# SWARMESH04.net
KiCad netlist of a schematic drawn in EAGLE
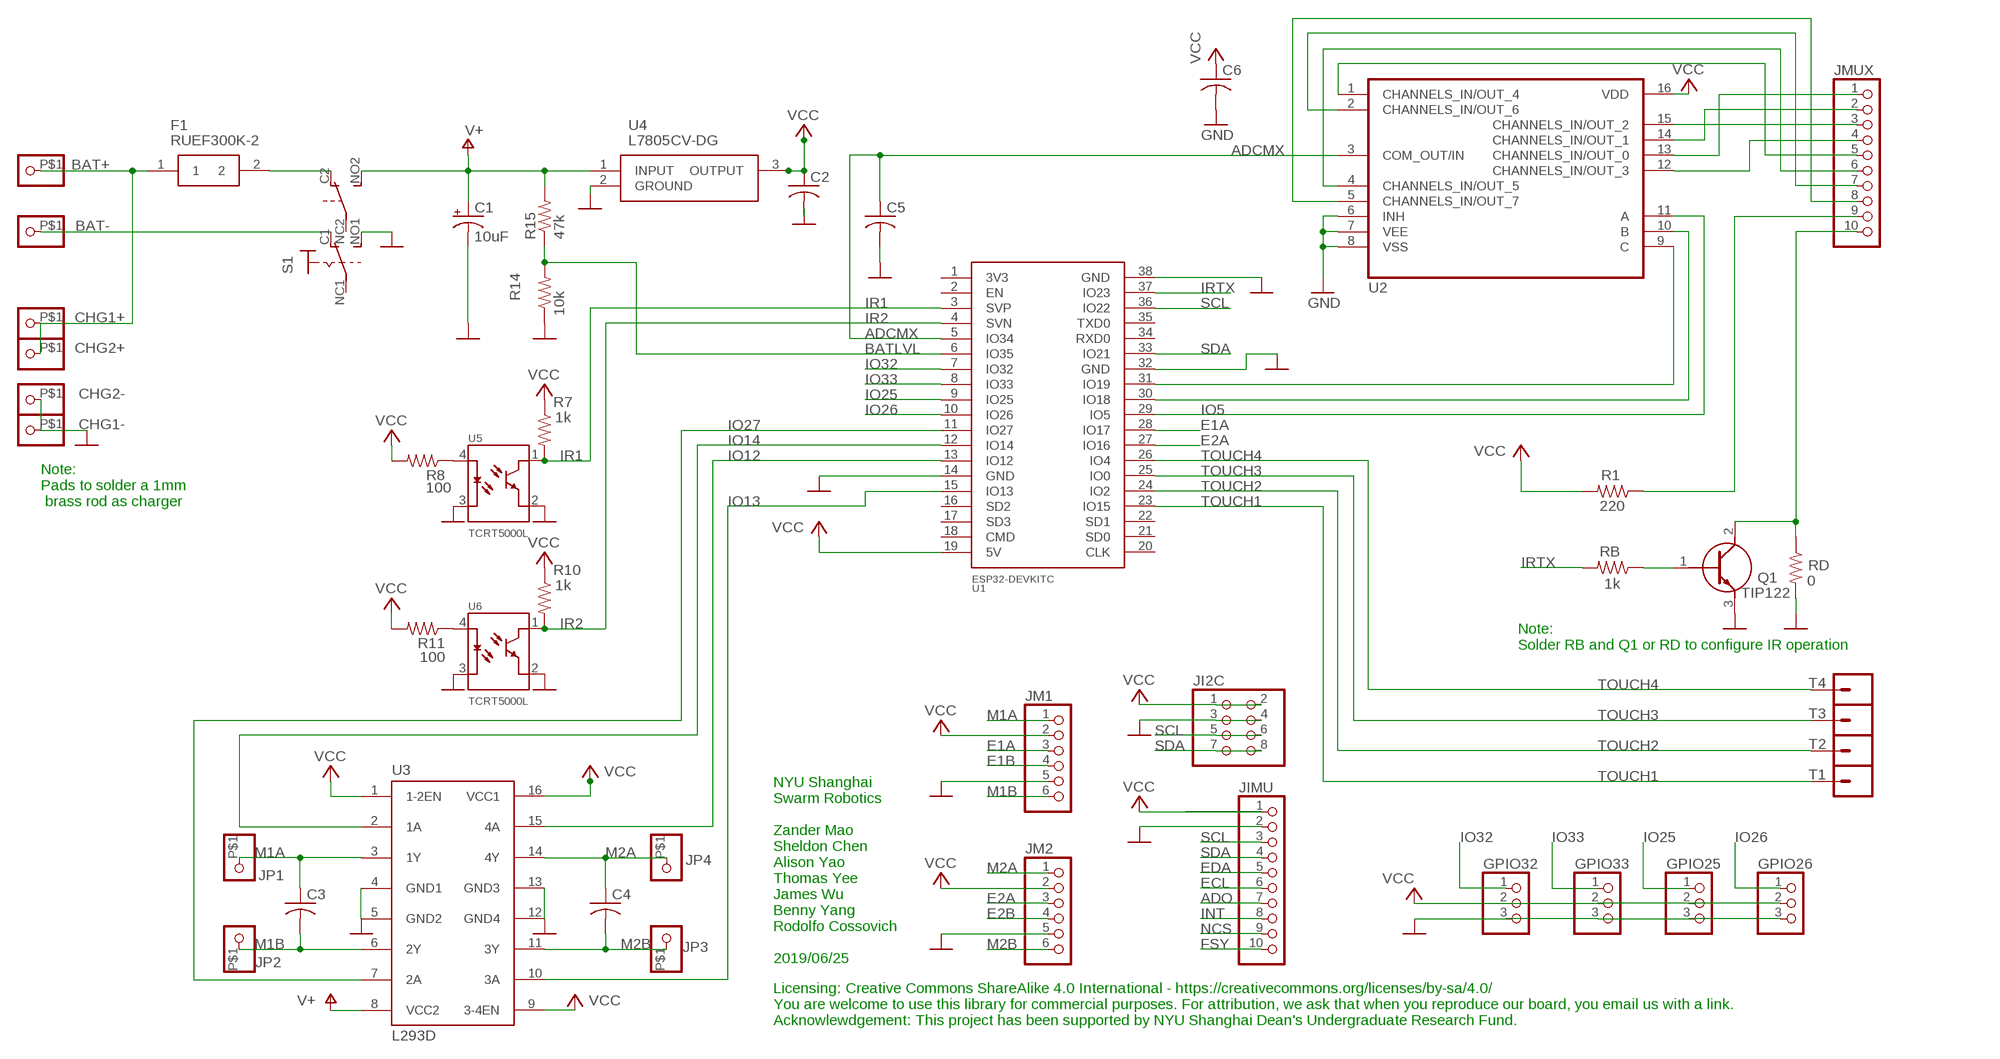
[diagram p0: schematic, sheet 1]

(export (version "E")
  (design (tool "Eeschema 10.0.6"))
  (components
    (comp (ref "BAT+")
      (value "PINHD-1X1-BIGPOGO")
      (footprint "eagle-import:1X1-BIGPOGO")
      (libsource (lib "eagle-import") (part "PINHD-1X1-BIGPOGO"))
    )
    (comp (ref "BAT-")
      (value "PINHD-1X1-BIGPOGO")
      (footprint "eagle-import:1X1-BIGPOGO")
      (libsource (lib "eagle-import") (part "PINHD-1X1-BIGPOGO"))
    )
    (comp (ref "C1")
      (value "10uF")
      (footprint "eagle-import:E2-5")
      (libsource (lib "eagle-import") (part "CPOL-USE2-5"))
    )
    (comp (ref "C2")
      (value "C-US025-030X050")
      (footprint "eagle-import:C025-030X050")
      (libsource (lib "eagle-import") (part "C-US025-030X050"))
    )
    (comp (ref "C3")
      (value "C-US025-025X050")
      (footprint "eagle-import:C025-025X050")
      (libsource (lib "eagle-import") (part "C-US025-025X050"))
    )
    (comp (ref "C4")
      (value "C-US025-025X050")
      (footprint "eagle-import:C025-025X050")
      (libsource (lib "eagle-import") (part "C-US025-025X050"))
    )
    (comp (ref "C5")
      (value "C-US025-030X050")
      (footprint "eagle-import:C025-030X050")
      (libsource (lib "eagle-import") (part "C-US025-030X050"))
    )
    (comp (ref "C6")
      (value "C-US025-025X050")
      (footprint "eagle-import:C025-025X050")
      (libsource (lib "eagle-import") (part "C-US025-025X050"))
    )
    (comp (ref "CHG1+")
      (value "PINHD-1X1-BIGPOGO")
      (footprint "eagle-import:1X1-BIGPOGO")
      (libsource (lib "eagle-import") (part "PINHD-1X1-BIGPOGO"))
    )
    (comp (ref "CHG1-")
      (value "PINHD-1X1-BIGPOGO")
      (footprint "eagle-import:1X1-BIGPOGO")
      (libsource (lib "eagle-import") (part "PINHD-1X1-BIGPOGO"))
    )
    (comp (ref "CHG2+")
      (value "PINHD-1X1-BIGPOGO")
      (footprint "eagle-import:1X1-BIGPOGO")
      (libsource (lib "eagle-import") (part "PINHD-1X1-BIGPOGO"))
    )
    (comp (ref "CHG2-")
      (value "PINHD-1X1-BIGPOGO")
      (footprint "eagle-import:1X1-BIGPOGO")
      (libsource (lib "eagle-import") (part "PINHD-1X1-BIGPOGO"))
    )
    (comp (ref "F1")
      (value "RUEF300K-2")
      (footprint "eagle-import:RUEF300K2")
      (libsource (lib "eagle-import") (part "RUEF300K-2"))
    )
    (comp (ref "GPIO25")
      (value "PINHD-1X3")
      (footprint "eagle-import:1X03")
      (libsource (lib "eagle-import") (part "PINHD-1X3"))
    )
    (comp (ref "GPIO26")
      (value "PINHD-1X3")
      (footprint "eagle-import:1X03")
      (libsource (lib "eagle-import") (part "PINHD-1X3"))
    )
    (comp (ref "GPIO32")
      (value "PINHD-1X3")
      (footprint "eagle-import:1X03")
      (libsource (lib "eagle-import") (part "PINHD-1X3"))
    )
    (comp (ref "GPIO33")
      (value "PINHD-1X3")
      (footprint "eagle-import:1X03")
      (libsource (lib "eagle-import") (part "PINHD-1X3"))
    )
    (comp (ref "JI2C")
      (value "PINHD-2X4")
      (footprint "eagle-import:2X04")
      (libsource (lib "eagle-import") (part "PINHD-2X4"))
    )
    (comp (ref "JIMU")
      (value "PINHD-1X10")
      (footprint "eagle-import:1X10-BIG")
      (libsource (lib "eagle-import") (part "PINHD-1X10"))
    )
    (comp (ref "JM1")
      (value "PINHD-1X6")
      (footprint "eagle-import:1X06")
      (libsource (lib "eagle-import") (part "PINHD-1X6"))
    )
    (comp (ref "JM2")
      (value "PINHD-1X6")
      (footprint "eagle-import:1X06")
      (libsource (lib "eagle-import") (part "PINHD-1X6"))
    )
    (comp (ref "JMUX")
      (value "PINHD-1X10")
      (footprint "eagle-import:1X10-BIG")
      (libsource (lib "eagle-import") (part "PINHD-1X10"))
    )
    (comp (ref "JP1")
      (value "PINHD-1X1-BIGPOGO")
      (footprint "eagle-import:1X1-BIGPOGO")
      (libsource (lib "eagle-import") (part "adafruit_420_PINHD-1X1-BIGPOGO"))
    )
    (comp (ref "JP2")
      (value "PINHD-1X1-BIGPOGO")
      (footprint "eagle-import:1X1-BIGPOGO")
      (libsource (lib "eagle-import") (part "adafruit_420_PINHD-1X1-BIGPOGO"))
    )
    (comp (ref "JP3")
      (value "PINHD-1X1-BIGPOGO")
      (footprint "eagle-import:1X1-BIGPOGO")
      (libsource (lib "eagle-import") (part "adafruit_420_PINHD-1X1-BIGPOGO"))
    )
    (comp (ref "JP4")
      (value "PINHD-1X1-BIGPOGO")
      (footprint "eagle-import:1X1-BIGPOGO")
      (libsource (lib "eagle-import") (part "adafruit_420_PINHD-1X1-BIGPOGO"))
    )
    (comp (ref "Q1")
      (value "TIP122")
      (footprint "eagle-import:TO270P460X1020X2008-3P")
      (fields (field (name "MOUSER_PART_NUMBER") "511-TIP122"))
      (libsource (lib "eagle-import") (part "TIP122"))
    )
    (comp (ref "R1")
      (value "220")
      (footprint "eagle-import:0207_9")
      (libsource (lib "eagle-import") (part "R-US_0207/9"))
    )
    (comp (ref "R7")
      (value "1k")
      (footprint "eagle-import:0207_9")
      (libsource (lib "eagle-import") (part "R-US_0207/9"))
    )
    (comp (ref "R8")
      (value "100")
      (footprint "eagle-import:0207_9")
      (libsource (lib "eagle-import") (part "R-US_0207/9"))
    )
    (comp (ref "R10")
      (value "1k")
      (footprint "eagle-import:0207_9")
      (libsource (lib "eagle-import") (part "R-US_0207/9"))
    )
    (comp (ref "R11")
      (value "100")
      (footprint "eagle-import:0207_9")
      (libsource (lib "eagle-import") (part "R-US_0207/9"))
    )
    (comp (ref "R14")
      (value "10k")
      (footprint "eagle-import:0207_9")
      (libsource (lib "eagle-import") (part "R-US_0207/9"))
    )
    (comp (ref "R15")
      (value "47k")
      (footprint "eagle-import:0207_9")
      (libsource (lib "eagle-import") (part "R-US_0207/9"))
    )
    (comp (ref "RB")
      (value "1k")
      (footprint "eagle-import:0207_9")
      (libsource (lib "eagle-import") (part "R-US_0207/9"))
    )
    (comp (ref "RD")
      (value "0")
      (footprint "eagle-import:0207_9")
      (libsource (lib "eagle-import") (part "R-US_0207/9"))
    )
    (comp (ref "S1")
      (value "SWITCH_320-938")
      (footprint "eagle-import:PS22F03")
      (libsource (lib "eagle-import") (part "SWITCH_320-938"))
    )
    (comp (ref "T1")
      (value "CONN_01SPRING-CONN")
      (footprint "eagle-import:SPRING-CONNECTOR")
      (libsource (lib "eagle-import") (part "CONN_01SPRING-CONN"))
    )
    (comp (ref "T2")
      (value "CONN_01SPRING-CONN")
      (footprint "eagle-import:SPRING-CONNECTOR")
      (libsource (lib "eagle-import") (part "CONN_01SPRING-CONN"))
    )
    (comp (ref "T3")
      (value "CONN_01SPRING-CONN")
      (footprint "eagle-import:SPRING-CONNECTOR")
      (libsource (lib "eagle-import") (part "CONN_01SPRING-CONN"))
    )
    (comp (ref "T4")
      (value "CONN_01SPRING-CONN")
      (footprint "eagle-import:SPRING-CONNECTOR")
      (libsource (lib "eagle-import") (part "CONN_01SPRING-CONN"))
    )
    (comp (ref "U1")
      (value "ESP32DEVKITC")
      (footprint "eagle-import:ESP32-DEVKITC")
      (libsource (lib "eagle-import") (part "ESP32DEVKITC"))
    )
    (comp (ref "U2")
      (value "CD4051BEE4")
      (footprint "eagle-import:CD4051BEE4DIP")
      (libsource (lib "eagle-import") (part "CD4051BEE4"))
    )
    (comp (ref "U3")
      (value "L293D")
      (footprint "eagle-import:DIL16")
      (libsource (lib "eagle-import") (part "L293D"))
    )
    (comp (ref "U4")
      (value "L7805CV-DG")
      (footprint "eagle-import:TO270P460X1020X2008-3P")
      (fields (field (name "MOUSER_PART_NUMBER") "511-L7805CV-DG") (field (name "RS_PART_NUMBER") "7931346P"))
      (libsource (lib "eagle-import") (part "L7805CV-DG"))
    )
    (comp (ref "U5")
      (value "TCRT5000L")
      (footprint "eagle-import:XDCR_TCRT5000L")
      (fields (field (name "MF") "Vishay Semiconductor"))
      (libsource (lib "eagle-import") (part "TCRT5000L"))
    )
    (comp (ref "U6")
      (value "TCRT5000L")
      (footprint "eagle-import:XDCR_TCRT5000L")
      (fields (field (name "MF") "Vishay Semiconductor"))
      (libsource (lib "eagle-import") (part "TCRT5000L"))
    )
  )
  (nets
    (net (code "1") (name "/ADCMX") (class "Default")
      (node (ref "C5") (pin "1") (pinfunction "1_1") (pintype "passive"))
      (node (ref "U1") (pin "5") (pinfunction "IO34_5") (pintype "bidirectional"))
      (node (ref "U2") (pin "3") (pinfunction "COM_OUT/IN_3") (pintype "bidirectional"))
    )
    (net (code "2") (name "/ADO") (class "Default")
      (node (ref "JIMU") (pin "7") (pinfunction "7_7") (pintype "passive"))
    )
    (net (code "3") (name "/BATLVL") (class "Default")
      (node (ref "R14") (pin "2") (pinfunction "2_2") (pintype "passive"))
      (node (ref "R15") (pin "1") (pinfunction "1_1") (pintype "passive"))
      (node (ref "U1") (pin "6") (pinfunction "IO35_6") (pintype "bidirectional"))
    )
    (net (code "4") (name "/E1A") (class "Default")
      (node (ref "JM1") (pin "3") (pinfunction "3_3") (pintype "passive"))
      (node (ref "U1") (pin "28") (pinfunction "IO17_28") (pintype "bidirectional"))
    )
    (net (code "5") (name "/E1B") (class "Default")
      (node (ref "JM1") (pin "4") (pinfunction "4_4") (pintype "passive"))
    )
    (net (code "6") (name "/E2A") (class "Default")
      (node (ref "JM2") (pin "3") (pinfunction "3_3") (pintype "passive"))
      (node (ref "U1") (pin "27") (pinfunction "IO16_27") (pintype "bidirectional"))
    )
    (net (code "7") (name "/E2B") (class "Default")
      (node (ref "JM2") (pin "4") (pinfunction "4_4") (pintype "passive"))
    )
    (net (code "8") (name "/ECL") (class "Default")
      (node (ref "JIMU") (pin "6") (pinfunction "6_6") (pintype "passive"))
    )
    (net (code "9") (name "/EDA") (class "Default")
      (node (ref "JIMU") (pin "5") (pinfunction "5_5") (pintype "passive"))
    )
    (net (code "10") (name "/FSY") (class "Default")
      (node (ref "JIMU") (pin "10") (pinfunction "10_10") (pintype "passive"))
    )
    (net (code "11") (name "/INT") (class "Default")
      (node (ref "JIMU") (pin "8") (pinfunction "8_8") (pintype "passive"))
    )
    (net (code "12") (name "/IO5") (class "Default")
      (node (ref "U1") (pin "29") (pinfunction "IO5_29") (pintype "bidirectional"))
      (node (ref "U2") (pin "11") (pinfunction "A_11") (pintype "input"))
    )
    (net (code "13") (name "/IO12") (class "Default")
      (node (ref "U1") (pin "13") (pinfunction "IO12_13") (pintype "bidirectional"))
      (node (ref "U3") (pin "15") (pinfunction "4A_15") (pintype "input"))
    )
    (net (code "14") (name "/IO13") (class "Default")
      (node (ref "U1") (pin "15") (pinfunction "IO13_15") (pintype "bidirectional"))
      (node (ref "U3") (pin "10") (pinfunction "3A_10") (pintype "input"))
    )
    (net (code "15") (name "/IO14") (class "Default")
      (node (ref "U1") (pin "12") (pinfunction "IO14_12") (pintype "bidirectional"))
      (node (ref "U3") (pin "2") (pinfunction "1A_2") (pintype "input"))
    )
    (net (code "16") (name "/IO25") (class "Default")
      (node (ref "GPIO25") (pin "1") (pinfunction "1_1") (pintype "passive"))
      (node (ref "U1") (pin "9") (pinfunction "IO25_9") (pintype "bidirectional"))
    )
    (net (code "17") (name "/IO26") (class "Default")
      (node (ref "GPIO26") (pin "1") (pinfunction "1_1") (pintype "passive"))
      (node (ref "U1") (pin "10") (pinfunction "IO26_10") (pintype "bidirectional"))
    )
    (net (code "18") (name "/IO27") (class "Default")
      (node (ref "U1") (pin "11") (pinfunction "IO27_11") (pintype "bidirectional"))
      (node (ref "U3") (pin "7") (pinfunction "2A_7") (pintype "input"))
    )
    (net (code "19") (name "/IO32") (class "Default")
      (node (ref "GPIO32") (pin "1") (pinfunction "1_1") (pintype "passive"))
      (node (ref "U1") (pin "7") (pinfunction "IO32_7") (pintype "bidirectional"))
    )
    (net (code "20") (name "/IO33") (class "Default")
      (node (ref "GPIO33") (pin "1") (pinfunction "1_1") (pintype "passive"))
      (node (ref "U1") (pin "8") (pinfunction "IO33_8") (pintype "bidirectional"))
    )
    (net (code "21") (name "/IR1") (class "Default")
      (node (ref "R7") (pin "2") (pinfunction "2_2") (pintype "passive"))
      (node (ref "U1") (pin "3") (pinfunction "SVP_3") (pintype "bidirectional"))
      (node (ref "U5") (pin "1") (pinfunction "CO_1") (pintype "passive"))
    )
    (net (code "22") (name "/IR2") (class "Default")
      (node (ref "R10") (pin "2") (pinfunction "2_2") (pintype "passive"))
      (node (ref "U1") (pin "4") (pinfunction "SVN_4") (pintype "bidirectional"))
      (node (ref "U6") (pin "1") (pinfunction "CO_1") (pintype "passive"))
    )
    (net (code "23") (name "/IRTX") (class "Default")
      (node (ref "RB") (pin "2") (pinfunction "2_2") (pintype "passive"))
      (node (ref "U1") (pin "37") (pinfunction "IO23_37") (pintype "bidirectional"))
    )
    (net (code "24") (name "/M1A") (class "Default")
      (node (ref "C3") (pin "1") (pinfunction "1_1") (pintype "passive"))
      (node (ref "JM1") (pin "1") (pinfunction "1_1") (pintype "passive"))
      (node (ref "JP1") (pin "P$1") (pinfunction "1_P$1") (pintype "passive"))
      (node (ref "U3") (pin "3") (pinfunction "1Y_3") (pintype "output"))
    )
    (net (code "25") (name "/M1B") (class "Default")
      (node (ref "C3") (pin "2") (pinfunction "2_2") (pintype "passive"))
      (node (ref "JM1") (pin "6") (pinfunction "6_6") (pintype "passive"))
      (node (ref "JP2") (pin "P$1") (pinfunction "1_P$1") (pintype "passive"))
      (node (ref "U3") (pin "6") (pinfunction "2Y_6") (pintype "output"))
    )
    (net (code "26") (name "/M2A") (class "Default")
      (node (ref "C4") (pin "1") (pinfunction "1_1") (pintype "passive"))
      (node (ref "JM2") (pin "1") (pinfunction "1_1") (pintype "passive"))
      (node (ref "JP4") (pin "P$1") (pinfunction "1_P$1") (pintype "passive"))
      (node (ref "U3") (pin "14") (pinfunction "4Y_14") (pintype "output"))
    )
    (net (code "27") (name "/M2B") (class "Default")
      (node (ref "C4") (pin "2") (pinfunction "2_2") (pintype "passive"))
      (node (ref "JM2") (pin "6") (pinfunction "6_6") (pintype "passive"))
      (node (ref "JP3") (pin "P$1") (pinfunction "1_P$1") (pintype "passive"))
      (node (ref "U3") (pin "11") (pinfunction "3Y_11") (pintype "output"))
    )
    (net (code "28") (name "/NCS") (class "Default")
      (node (ref "JIMU") (pin "9") (pinfunction "9_9") (pintype "passive"))
    )
    (net (code "29") (name "/SCL") (class "Default")
      (node (ref "JI2C") (pin "5") (pinfunction "5_5") (pintype "passive"))
      (node (ref "JI2C") (pin "6") (pinfunction "6_6") (pintype "passive"))
      (node (ref "JIMU") (pin "3") (pinfunction "3_3") (pintype "passive"))
      (node (ref "U1") (pin "36") (pinfunction "IO22_36") (pintype "bidirectional"))
    )
    (net (code "30") (name "/SDA") (class "Default")
      (node (ref "JI2C") (pin "7") (pinfunction "7_7") (pintype "passive"))
      (node (ref "JI2C") (pin "8") (pinfunction "8_8") (pintype "passive"))
      (node (ref "JIMU") (pin "4") (pinfunction "4_4") (pintype "passive"))
      (node (ref "U1") (pin "33") (pinfunction "IO21_33") (pintype "bidirectional"))
    )
    (net (code "31") (name "/TOUCH1") (class "Default")
      (node (ref "T1") (pin "P$2") (pinfunction "1_P$2") (pintype "passive"))
      (node (ref "U1") (pin "23") (pinfunction "IO15_23") (pintype "bidirectional"))
    )
    (net (code "32") (name "/TOUCH2") (class "Default")
      (node (ref "T2") (pin "P$2") (pinfunction "1_P$2") (pintype "passive"))
      (node (ref "U1") (pin "24") (pinfunction "IO2_24") (pintype "bidirectional"))
    )
    (net (code "33") (name "/TOUCH3") (class "Default")
      (node (ref "T3") (pin "P$2") (pinfunction "1_P$2") (pintype "passive"))
      (node (ref "U1") (pin "25") (pinfunction "IO0_25") (pintype "bidirectional"))
    )
    (net (code "34") (name "/TOUCH4") (class "Default")
      (node (ref "T4") (pin "P$2") (pinfunction "1_P$2") (pintype "passive"))
      (node (ref "U1") (pin "26") (pinfunction "IO4_26") (pintype "bidirectional"))
    )
    (net (code "35") (name "GND") (class "Default")
      (node (ref "C1") (pin "-") (pinfunction "-_-") (pintype "passive"))
      (node (ref "C2") (pin "2") (pinfunction "2_2") (pintype "passive"))
      (node (ref "C5") (pin "2") (pinfunction "2_2") (pintype "passive"))
      (node (ref "C6") (pin "2") (pinfunction "2_2") (pintype "passive"))
      (node (ref "CHG1-") (pin "P$1") (pinfunction "1_P$1") (pintype "passive"))
      (node (ref "CHG2-") (pin "P$1") (pinfunction "1_P$1") (pintype "passive"))
      (node (ref "GPIO25") (pin "3") (pinfunction "3_3") (pintype "passive"))
      (node (ref "GPIO26") (pin "3") (pinfunction "3_3") (pintype "passive"))
      (node (ref "GPIO32") (pin "3") (pinfunction "3_3") (pintype "passive"))
      (node (ref "GPIO33") (pin "3") (pinfunction "3_3") (pintype "passive"))
      (node (ref "JI2C") (pin "3") (pinfunction "3_3") (pintype "passive"))
      (node (ref "JI2C") (pin "4") (pinfunction "4_4") (pintype "passive"))
      (node (ref "JIMU") (pin "2") (pinfunction "2_2") (pintype "passive"))
      (node (ref "JM1") (pin "5") (pinfunction "5_5") (pintype "passive"))
      (node (ref "JM2") (pin "5") (pinfunction "5_5") (pintype "passive"))
      (node (ref "Q1") (pin "3") (pinfunction "E_3") (pintype "bidirectional"))
      (node (ref "R14") (pin "1") (pinfunction "1_1") (pintype "passive"))
      (node (ref "RD") (pin "2") (pinfunction "2_2") (pintype "passive"))
      (node (ref "S1") (pin "NO1") (pinfunction "S_NO1") (pintype "passive"))
      (node (ref "U1") (pin "14") (pinfunction "GND_14") (pintype "bidirectional"))
      (node (ref "U1") (pin "32") (pinfunction "GND_32") (pintype "bidirectional"))
      (node (ref "U1") (pin "38") (pinfunction "GND_38") (pintype "bidirectional"))
      (node (ref "U2") (pin "6") (pinfunction "INH_6") (pintype "input"))
      (node (ref "U2") (pin "7") (pinfunction "VEE_7") (pintype "power_in"))
      (node (ref "U2") (pin "8") (pinfunction "VSS_8") (pintype "power_in"))
      (node (ref "U3") (pin "12") (pinfunction "GND4_12") (pintype "power_in"))
      (node (ref "U3") (pin "13") (pinfunction "GND3_13") (pintype "power_in"))
      (node (ref "U3") (pin "4") (pinfunction "GND1_4") (pintype "power_in"))
      (node (ref "U3") (pin "5") (pinfunction "GND2_5") (pintype "power_in"))
      (node (ref "U4") (pin "2") (pinfunction "GROUND_2") (pintype "bidirectional"))
      (node (ref "U5") (pin "2") (pinfunction "E_2") (pintype "passive"))
      (node (ref "U5") (pin "3") (pinfunction "C_3") (pintype "passive"))
      (node (ref "U6") (pin "2") (pinfunction "E_2") (pintype "passive"))
      (node (ref "U6") (pin "3") (pinfunction "C_3") (pintype "passive"))
    )
    (net (code "36") (name "Net-(BAT+-1)") (class "Default")
      (node (ref "BAT+") (pin "P$1") (pinfunction "1_P$1") (pintype "passive"))
      (node (ref "CHG1+") (pin "P$1") (pinfunction "1_P$1") (pintype "passive"))
      (node (ref "CHG2+") (pin "P$1") (pinfunction "1_P$1") (pintype "passive"))
      (node (ref "F1") (pin "1") (pinfunction "1_1") (pintype "bidirectional"))
    )
    (net (code "37") (name "Net-(BAT--1)") (class "Default")
      (node (ref "BAT-") (pin "P$1") (pinfunction "1_P$1") (pintype "passive"))
      (node (ref "S1") (pin "C1") (pinfunction "O_C1") (pintype "passive"))
    )
    (net (code "38") (name "Net-(JMUX-Pad9)") (class "Default")
      (node (ref "JMUX") (pin "9") (pinfunction "9_9") (pintype "passive"))
      (node (ref "R1") (pin "1") (pinfunction "1_1") (pintype "passive"))
    )
    (net (code "39") (name "Net-(Q1-B)") (class "Default")
      (node (ref "Q1") (pin "1") (pinfunction "B_1") (pintype "bidirectional"))
      (node (ref "RB") (pin "1") (pinfunction "1_1") (pintype "passive"))
    )
    (net (code "40") (name "Net-(Q1-C)") (class "Default")
      (node (ref "JMUX") (pin "10") (pinfunction "10_10") (pintype "passive"))
      (node (ref "Q1") (pin "2") (pinfunction "C_2") (pintype "bidirectional"))
      (node (ref "RD") (pin "1") (pinfunction "1_1") (pintype "passive"))
    )
    (net (code "41") (name "Net-(S1B-O)") (class "Default")
      (node (ref "F1") (pin "2") (pinfunction "2_2") (pintype "bidirectional"))
      (node (ref "S1") (pin "C2") (pinfunction "O_C2") (pintype "passive"))
    )
    (net (code "42") (name "Net-(U1-IO18)") (class "Default")
      (node (ref "U1") (pin "30") (pinfunction "IO18_30") (pintype "bidirectional"))
      (node (ref "U2") (pin "10") (pinfunction "B_10") (pintype "input"))
    )
    (net (code "43") (name "Net-(U1-IO19)") (class "Default")
      (node (ref "U1") (pin "31") (pinfunction "IO19_31") (pintype "bidirectional"))
      (node (ref "U2") (pin "9") (pinfunction "C_9") (pintype "input"))
    )
    (net (code "44") (name "Net-(U2-CHANNELS_IN{slash}OUT_0)") (class "Default")
      (node (ref "JMUX") (pin "1") (pinfunction "1_1") (pintype "passive"))
      (node (ref "U2") (pin "13") (pinfunction "CHANNELS_IN/OUT_0_13") (pintype "bidirectional"))
    )
    (net (code "45") (name "Net-(U2-CHANNELS_IN{slash}OUT_1)") (class "Default")
      (node (ref "JMUX") (pin "2") (pinfunction "2_2") (pintype "passive"))
      (node (ref "U2") (pin "14") (pinfunction "CHANNELS_IN/OUT_1_14") (pintype "bidirectional"))
    )
    (net (code "46") (name "Net-(U2-CHANNELS_IN{slash}OUT_2)") (class "Default")
      (node (ref "JMUX") (pin "3") (pinfunction "3_3") (pintype "passive"))
      (node (ref "U2") (pin "15") (pinfunction "CHANNELS_IN/OUT_2_15") (pintype "bidirectional"))
    )
    (net (code "47") (name "Net-(U2-CHANNELS_IN{slash}OUT_3)") (class "Default")
      (node (ref "JMUX") (pin "4") (pinfunction "4_4") (pintype "passive"))
      (node (ref "U2") (pin "12") (pinfunction "CHANNELS_IN/OUT_3_12") (pintype "bidirectional"))
    )
    (net (code "48") (name "Net-(U2-CHANNELS_IN{slash}OUT_4)") (class "Default")
      (node (ref "JMUX") (pin "5") (pinfunction "5_5") (pintype "passive"))
      (node (ref "U2") (pin "1") (pinfunction "CHANNELS_IN/OUT_4_1") (pintype "bidirectional"))
    )
    (net (code "49") (name "Net-(U2-CHANNELS_IN{slash}OUT_5)") (class "Default")
      (node (ref "JMUX") (pin "6") (pinfunction "6_6") (pintype "passive"))
      (node (ref "U2") (pin "4") (pinfunction "CHANNELS_IN/OUT_5_4") (pintype "bidirectional"))
    )
    (net (code "50") (name "Net-(U2-CHANNELS_IN{slash}OUT_6)") (class "Default")
      (node (ref "JMUX") (pin "7") (pinfunction "7_7") (pintype "passive"))
      (node (ref "U2") (pin "2") (pinfunction "CHANNELS_IN/OUT_6_2") (pintype "bidirectional"))
    )
    (net (code "51") (name "Net-(U2-CHANNELS_IN{slash}OUT_7)") (class "Default")
      (node (ref "JMUX") (pin "8") (pinfunction "8_8") (pintype "passive"))
      (node (ref "U2") (pin "5") (pinfunction "CHANNELS_IN/OUT_7_5") (pintype "bidirectional"))
    )
    (net (code "52") (name "Net-(U5-A)") (class "Default")
      (node (ref "R8") (pin "1") (pinfunction "1_1") (pintype "passive"))
      (node (ref "U5") (pin "4") (pinfunction "A_4") (pintype "passive"))
    )
    (net (code "53") (name "Net-(U6-A)") (class "Default")
      (node (ref "R11") (pin "1") (pinfunction "1_1") (pintype "passive"))
      (node (ref "U6") (pin "4") (pinfunction "A_4") (pintype "passive"))
    )
    (net (code "54") (name "V+") (class "Default")
      (node (ref "C1") (pin "+") (pinfunction "+_+") (pintype "passive"))
      (node (ref "R15") (pin "2") (pinfunction "2_2") (pintype "passive"))
      (node (ref "S1") (pin "NO2") (pinfunction "S_NO2") (pintype "passive"))
      (node (ref "U3") (pin "8") (pinfunction "VCC2_8") (pintype "power_in"))
      (node (ref "U4") (pin "1") (pinfunction "INPUT_1") (pintype "input"))
    )
    (net (code "55") (name "VCC") (class "Default")
      (node (ref "C2") (pin "1") (pinfunction "1_1") (pintype "passive"))
      (node (ref "C6") (pin "1") (pinfunction "1_1") (pintype "passive"))
      (node (ref "GPIO25") (pin "2") (pinfunction "2_2") (pintype "passive"))
      (node (ref "GPIO26") (pin "2") (pinfunction "2_2") (pintype "passive"))
      (node (ref "GPIO32") (pin "2") (pinfunction "2_2") (pintype "passive"))
      (node (ref "GPIO33") (pin "2") (pinfunction "2_2") (pintype "passive"))
      (node (ref "JI2C") (pin "1") (pinfunction "1_1") (pintype "passive"))
      (node (ref "JI2C") (pin "2") (pinfunction "2_2") (pintype "passive"))
      (node (ref "JIMU") (pin "1") (pinfunction "1_1") (pintype "passive"))
      (node (ref "JM1") (pin "2") (pinfunction "2_2") (pintype "passive"))
      (node (ref "JM2") (pin "2") (pinfunction "2_2") (pintype "passive"))
      (node (ref "R1") (pin "2") (pinfunction "2_2") (pintype "passive"))
      (node (ref "R10") (pin "1") (pinfunction "1_1") (pintype "passive"))
      (node (ref "R11") (pin "2") (pinfunction "2_2") (pintype "passive"))
      (node (ref "R7") (pin "1") (pinfunction "1_1") (pintype "passive"))
      (node (ref "R8") (pin "2") (pinfunction "2_2") (pintype "passive"))
      (node (ref "U1") (pin "19") (pinfunction "5V_19") (pintype "bidirectional"))
      (node (ref "U2") (pin "16") (pinfunction "VDD_16") (pintype "power_in"))
      (node (ref "U3") (pin "1") (pinfunction "1-2EN_1") (pintype "input"))
      (node (ref "U3") (pin "16") (pinfunction "VCC1_16") (pintype "power_in"))
      (node (ref "U3") (pin "9") (pinfunction "3-4EN_9") (pintype "input"))
      (node (ref "U4") (pin "3") (pinfunction "OUTPUT_3") (pintype "output"))
    )
    (net (code "56") (name "unconnected-(S1A-P-PadNC1)") (class "Default")
      (node (ref "S1") (pin "NC1") (pinfunction "P_NC1") (pintype "passive"))
    )
    (net (code "57") (name "unconnected-(S1B-P-PadNC2)") (class "Default")
      (node (ref "S1") (pin "NC2") (pinfunction "P_NC2") (pintype "passive"))
    )
    (net (code "58") (name "unconnected-(U1-3V3-Pad1)") (class "Default")
      (node (ref "U1") (pin "1") (pinfunction "3V3_1") (pintype "bidirectional"))
    )
    (net (code "59") (name "unconnected-(U1-CLK-Pad20)") (class "Default")
      (node (ref "U1") (pin "20") (pinfunction "CLK_20") (pintype "bidirectional"))
    )
    (net (code "60") (name "unconnected-(U1-CMD-Pad18)") (class "Default")
      (node (ref "U1") (pin "18") (pinfunction "CMD_18") (pintype "bidirectional"))
    )
    (net (code "61") (name "unconnected-(U1-EN-Pad2)") (class "Default")
      (node (ref "U1") (pin "2") (pinfunction "EN_2") (pintype "bidirectional"))
    )
    (net (code "62") (name "unconnected-(U1-RXD0-Pad34)") (class "Default")
      (node (ref "U1") (pin "34") (pinfunction "RXD0_34") (pintype "bidirectional"))
    )
    (net (code "63") (name "unconnected-(U1-SD0-Pad21)") (class "Default")
      (node (ref "U1") (pin "21") (pinfunction "SD0_21") (pintype "bidirectional"))
    )
    (net (code "64") (name "unconnected-(U1-SD1-Pad22)") (class "Default")
      (node (ref "U1") (pin "22") (pinfunction "SD1_22") (pintype "bidirectional"))
    )
    (net (code "65") (name "unconnected-(U1-SD2-Pad16)") (class "Default")
      (node (ref "U1") (pin "16") (pinfunction "SD2_16") (pintype "bidirectional"))
    )
    (net (code "66") (name "unconnected-(U1-SD3-Pad17)") (class "Default")
      (node (ref "U1") (pin "17") (pinfunction "SD3_17") (pintype "bidirectional"))
    )
    (net (code "67") (name "unconnected-(U1-TXD0-Pad35)") (class "Default")
      (node (ref "U1") (pin "35") (pinfunction "TXD0_35") (pintype "bidirectional"))
    )
  )
)
